# MicroMultimeter_EXP_Sch.net
KiCad netlist of a schematic drawn in Altium Designer
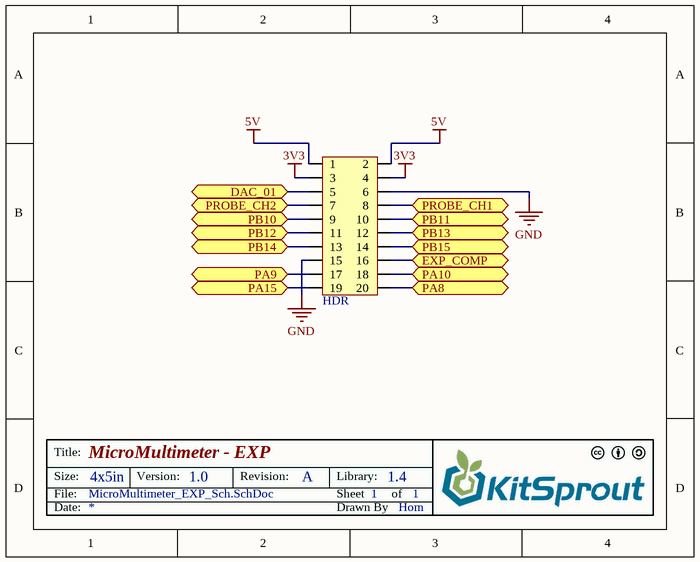
[diagram p0: MicroMultimeter_EXP_Sch.SchDoc]

(export (version "E")
  (design (tool "Eeschema 10.0.6"))
  (components
    (comp (ref "HDR")
      (value "HDR2x10_2.54")
      (footprint "PCB_ConnectorHDR:HDR2X10_2.54_180HF")
      (description "Header")
      (libsource (lib "SCH_ConnectorHDR") (part "HDR2x10_2.54"))
    )
  )
  (nets
    (net (code "1") (name "/DAC_01") (class "Default")
      (node (ref "HDR") (pin "5") (pinfunction "5_5") (pintype "passive"))
    )
    (net (code "2") (name "/EXP_COMP") (class "Default")
      (node (ref "HDR") (pin "16") (pinfunction "16_16") (pintype "passive"))
    )
    (net (code "3") (name "/PA8") (class "Default")
      (node (ref "HDR") (pin "20") (pinfunction "20_20") (pintype "passive"))
    )
    (net (code "4") (name "/PA9") (class "Default")
      (node (ref "HDR") (pin "17") (pinfunction "17_17") (pintype "passive"))
    )
    (net (code "5") (name "/PA10") (class "Default")
      (node (ref "HDR") (pin "18") (pinfunction "18_18") (pintype "passive"))
    )
    (net (code "6") (name "/PA15") (class "Default")
      (node (ref "HDR") (pin "19") (pinfunction "19_19") (pintype "passive"))
    )
    (net (code "7") (name "/PB10") (class "Default")
      (node (ref "HDR") (pin "9") (pinfunction "9_9") (pintype "passive"))
    )
    (net (code "8") (name "/PB11") (class "Default")
      (node (ref "HDR") (pin "10") (pinfunction "10_10") (pintype "passive"))
    )
    (net (code "9") (name "/PB12") (class "Default")
      (node (ref "HDR") (pin "11") (pinfunction "11_11") (pintype "passive"))
    )
    (net (code "10") (name "/PB13") (class "Default")
      (node (ref "HDR") (pin "12") (pinfunction "12_12") (pintype "passive"))
    )
    (net (code "11") (name "/PB14") (class "Default")
      (node (ref "HDR") (pin "13") (pinfunction "13_13") (pintype "passive"))
    )
    (net (code "12") (name "/PB15") (class "Default")
      (node (ref "HDR") (pin "14") (pinfunction "14_14") (pintype "passive"))
    )
    (net (code "13") (name "/PROBE_CH1") (class "Default")
      (node (ref "HDR") (pin "8") (pinfunction "8_8") (pintype "passive"))
    )
    (net (code "14") (name "/PROBE_CH2") (class "Default")
      (node (ref "HDR") (pin "7") (pinfunction "7_7") (pintype "passive"))
    )
    (net (code "15") (name "3V3") (class "Default")
      (node (ref "HDR") (pin "3") (pinfunction "3_3") (pintype "passive"))
      (node (ref "HDR") (pin "4") (pinfunction "4_4") (pintype "passive"))
    )
    (net (code "16") (name "5V") (class "Default")
      (node (ref "HDR") (pin "1") (pinfunction "1_1") (pintype "passive"))
      (node (ref "HDR") (pin "2") (pinfunction "2_2") (pintype "passive"))
    )
    (net (code "17") (name "GND") (class "Default")
      (node (ref "HDR") (pin "15") (pinfunction "15_15") (pintype "passive"))
      (node (ref "HDR") (pin "6") (pinfunction "6_6") (pintype "passive"))
    )
  )
)
